# pressure_temp.net
KiCad netlist of a schematic drawn in EAGLE
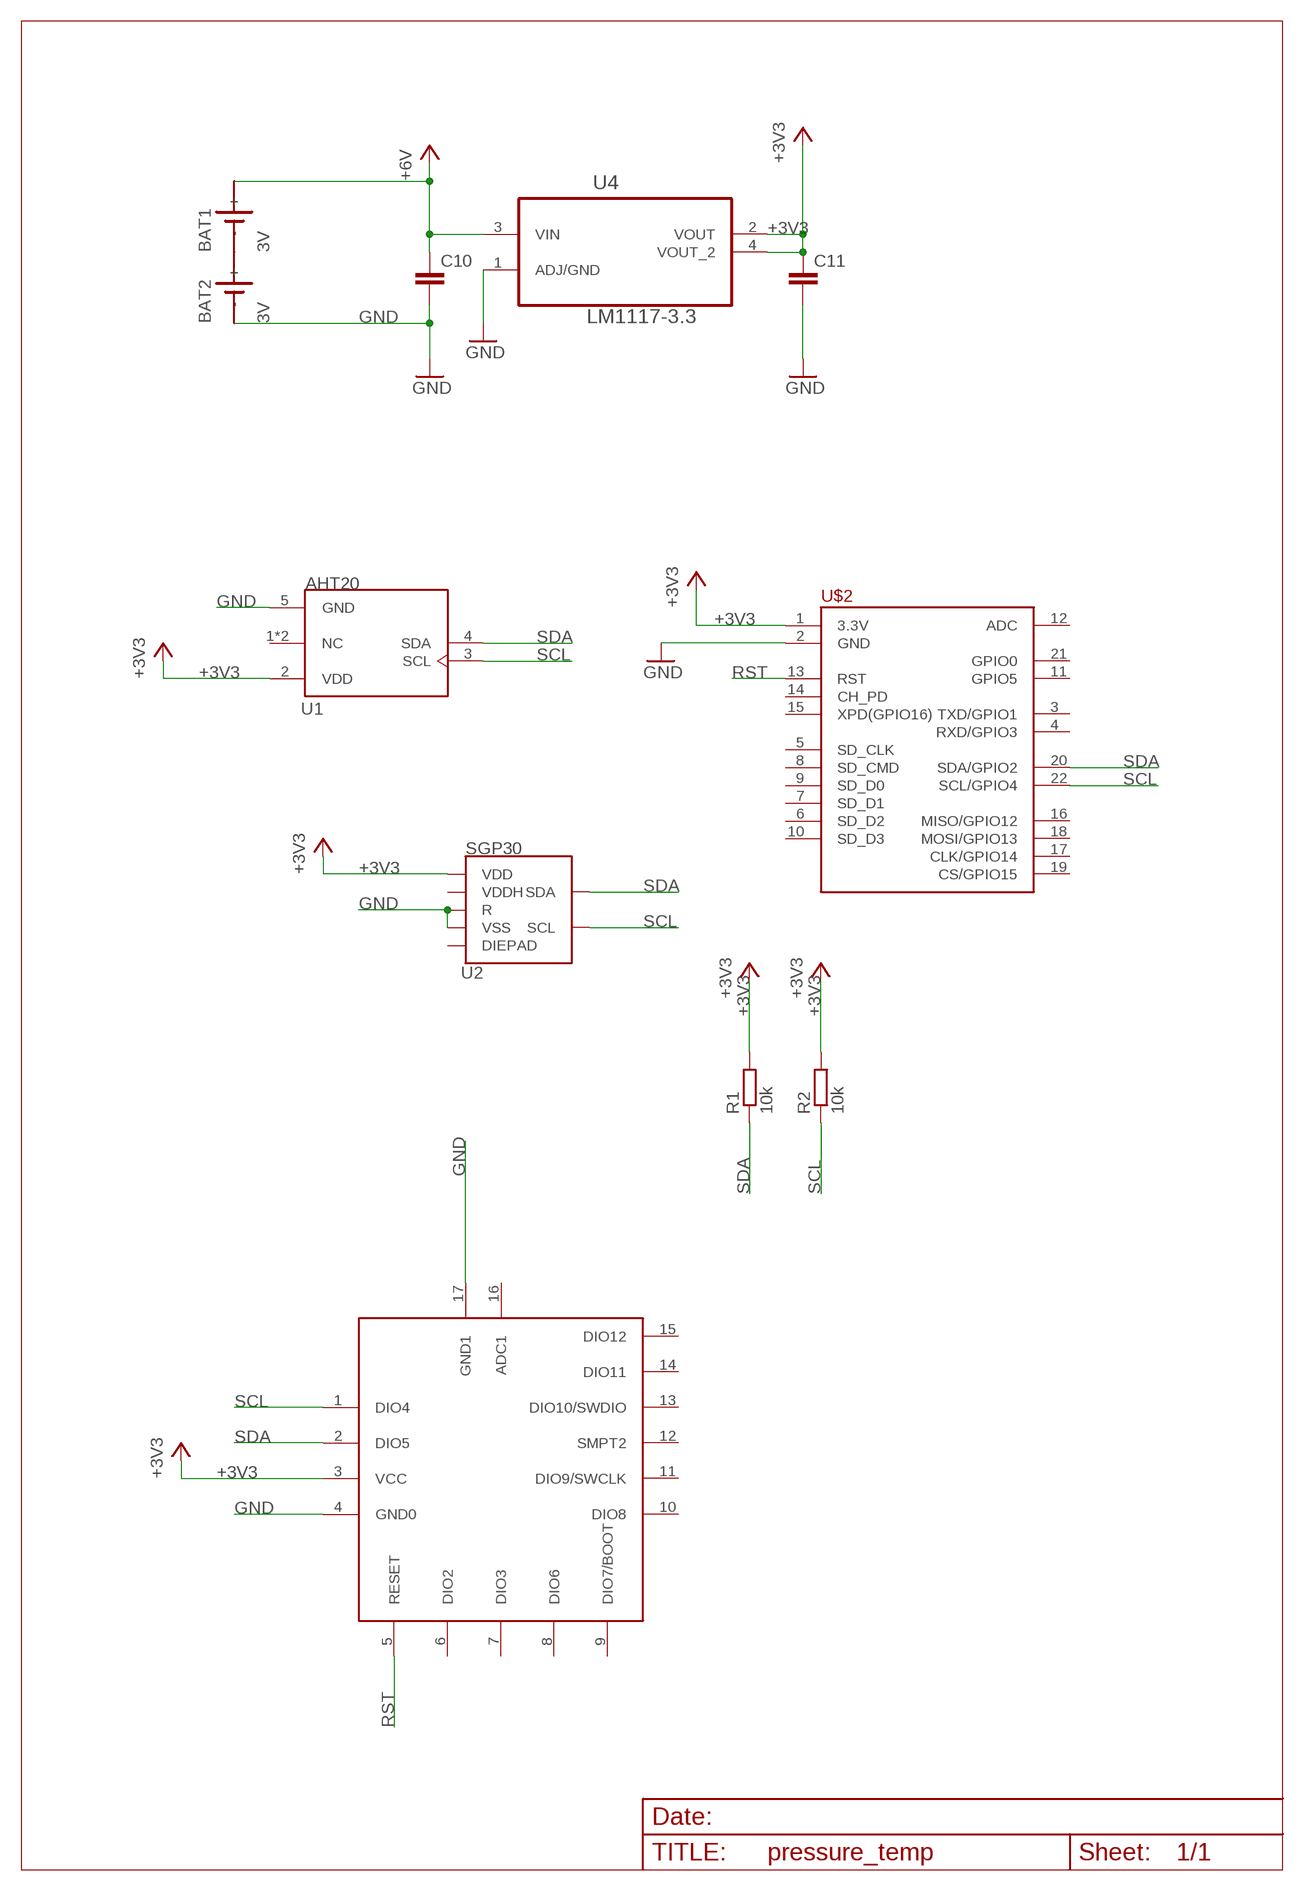
[diagram p0: schematic, sheet 1]

(export (version "E")
  (design (tool "Eeschema 10.0.6"))
  (components
    (comp (ref "BAT1")
      (value "3V")
      (footprint "eagle-import:SN2032")
      (libsource (lib "eagle-import") (part "SN2032"))
    )
    (comp (ref "BAT2")
      (value "3V")
      (footprint "eagle-import:SN2032")
      (libsource (lib "eagle-import") (part "SN2032"))
    )
    (comp (ref "C10")
      (value "47u")
      (footprint "eagle-import:C1206")
      (libsource (lib "eagle-import") (part "C-EUC1206"))
    )
    (comp (ref "C11")
      (value "10u")
      (footprint "eagle-import:C1206")
      (libsource (lib "eagle-import") (part "C-EUC1206"))
    )
    (comp (ref "R1")
      (value "10k")
      (footprint "eagle-import:R0402")
      (libsource (lib "eagle-import") (part "R-EU_R0402"))
    )
    (comp (ref "R2")
      (value "10k")
      (footprint "eagle-import:R0402")
      (libsource (lib "eagle-import") (part "R-EU_R0402"))
    )
    (comp (ref "U$1")
      (value "BLUENRG-234BLEMODULE")
      (footprint "eagle-import:BLUENRG-234BLEMODULE")
      (libsource (lib "eagle-import") (part "BLUENRG-234BLEMODULE"))
    )
    (comp (ref "U$2")
      (value "OLIMEX_MOD-WIFI-ESP8266-DEV>PINS-OUTSIDE")
      (footprint "eagle-import:OLIMEX_MOD-WIFI-ESP8266-DEV-PINS-OUTSIDE")
      (libsource (lib "eagle-import") (part "OLIMEX_MOD-WIFI-ESP8266-DEV{gt}PINS-OUTSIDE"))
    )
    (comp (ref "U1")
      (value "AHT20")
      (footprint "eagle-import:PSON100P300X300X110-6N")
      (fields (field (name "MF") "Asair"))
      (libsource (lib "eagle-import") (part "AHT20"))
    )
    (comp (ref "U2")
      (value "SGP30")
      (footprint "eagle-import:SGP30")
      (fields (field (name "MF") "Sensirion AG"))
      (libsource (lib "eagle-import") (part "SGP30"))
    )
    (comp (ref "U4")
      (value "LM1117-3.3")
      (footprint "eagle-import:SOT230")
      (fields (field (name "MF") "Texas Instruments"))
      (libsource (lib "eagle-import") (part "LM1117-3.3"))
    )
  )
  (nets
    (net (code "1") (name "+3V3") (class "Default")
      (node (ref "C11") (pin "1") (pinfunction "1_1") (pintype "passive"))
      (node (ref "R1") (pin "2") (pinfunction "2_2") (pintype "passive"))
      (node (ref "R2") (pin "2") (pinfunction "2_2") (pintype "passive"))
      (node (ref "U$1") (pin "3") (pinfunction "VCC_3") (pintype "bidirectional"))
      (node (ref "U$2") (pin "1") (pinfunction "3.3V_1") (pintype "power_in"))
      (node (ref "U1") (pin "2") (pinfunction "VDD_2") (pintype "power_in"))
      (node (ref "U2") (pin "1") (pinfunction "VDD_1") (pintype "bidirectional"))
      (node (ref "U4") (pin "2") (pinfunction "VOUT_2") (pintype "output"))
      (node (ref "U4") (pin "4") (pinfunction "VOUT_2_4") (pintype "output"))
    )
    (net (code "2") (name "+6V") (class "Default")
      (node (ref "BAT1") (pin "+") (pinfunction "+_+") (pintype "passive"))
      (node (ref "C10") (pin "1") (pinfunction "1_1") (pintype "passive"))
      (node (ref "U4") (pin "3") (pinfunction "VIN_3") (pintype "input"))
    )
    (net (code "3") (name "/RST") (class "Default")
      (node (ref "U$1") (pin "5") (pinfunction "RESET_5") (pintype "bidirectional"))
      (node (ref "U$2") (pin "13") (pinfunction "RST_13") (pintype "input"))
    )
    (net (code "4") (name "/SCL") (class "Default")
      (node (ref "R2") (pin "1") (pinfunction "1_1") (pintype "passive"))
      (node (ref "U$1") (pin "1") (pinfunction "DIO4_1") (pintype "bidirectional"))
      (node (ref "U$2") (pin "22") (pinfunction "SCL/GPIO4_22") (pintype "bidirectional"))
      (node (ref "U1") (pin "3") (pinfunction "SCL_3") (pintype "input"))
      (node (ref "U2") (pin "6") (pinfunction "SCL_6") (pintype "bidirectional"))
    )
    (net (code "5") (name "/SDA") (class "Default")
      (node (ref "R1") (pin "1") (pinfunction "1_1") (pintype "passive"))
      (node (ref "U$1") (pin "2") (pinfunction "DIO5_2") (pintype "bidirectional"))
      (node (ref "U$2") (pin "20") (pinfunction "SDA/GPIO2_20") (pintype "bidirectional"))
      (node (ref "U1") (pin "4") (pinfunction "SDA_4") (pintype "bidirectional"))
      (node (ref "U2") (pin "3") (pinfunction "SDA_3") (pintype "bidirectional"))
    )
    (net (code "6") (name "GND") (class "Default")
      (node (ref "BAT2") (pin "-") (pinfunction "-_-") (pintype "passive"))
      (node (ref "C10") (pin "2") (pinfunction "2_2") (pintype "passive"))
      (node (ref "C11") (pin "2") (pinfunction "2_2") (pintype "passive"))
      (node (ref "U$1") (pin "17") (pinfunction "GND1_17") (pintype "bidirectional"))
      (node (ref "U$1") (pin "4") (pinfunction "GND0_4") (pintype "bidirectional"))
      (node (ref "U$2") (pin "2") (pinfunction "GND_2") (pintype "power_in"))
      (node (ref "U1") (pin "5") (pinfunction "GND_5") (pintype "power_in"))
      (node (ref "U2") (pin "2") (pinfunction "VSS_2") (pintype "bidirectional"))
      (node (ref "U2") (pin "4") (pinfunction "R_4") (pintype "bidirectional"))
      (node (ref "U4") (pin "1") (pinfunction "ADJ/GND_1") (pintype "passive"))
    )
    (net (code "7") (name "Net-(BAT1-Pad-)") (class "Default")
      (node (ref "BAT1") (pin "-") (pinfunction "-_-") (pintype "passive"))
      (node (ref "BAT2") (pin "+") (pinfunction "+_+") (pintype "passive"))
    )
    (net (code "8") (name "unconnected-(U$1-ADC1-Pad16)") (class "Default")
      (node (ref "U$1") (pin "16") (pinfunction "ADC1_16") (pintype "bidirectional"))
    )
    (net (code "9") (name "unconnected-(U$1-DIO2-Pad6)") (class "Default")
      (node (ref "U$1") (pin "6") (pinfunction "DIO2_6") (pintype "bidirectional"))
    )
    (net (code "10") (name "unconnected-(U$1-DIO3-Pad7)") (class "Default")
      (node (ref "U$1") (pin "7") (pinfunction "DIO3_7") (pintype "bidirectional"))
    )
    (net (code "11") (name "unconnected-(U$1-DIO6-Pad8)") (class "Default")
      (node (ref "U$1") (pin "8") (pinfunction "DIO6_8") (pintype "bidirectional"))
    )
    (net (code "12") (name "unconnected-(U$1-DIO7{slash}BOOT-Pad9)") (class "Default")
      (node (ref "U$1") (pin "9") (pinfunction "DIO7/BOOT_9") (pintype "bidirectional"))
    )
    (net (code "13") (name "unconnected-(U$1-DIO8-Pad10)") (class "Default")
      (node (ref "U$1") (pin "10") (pinfunction "DIO8_10") (pintype "bidirectional"))
    )
    (net (code "14") (name "unconnected-(U$1-DIO9{slash}SWCLK-Pad11)") (class "Default")
      (node (ref "U$1") (pin "11") (pinfunction "DIO9/SWCLK_11") (pintype "bidirectional"))
    )
    (net (code "15") (name "unconnected-(U$1-DIO10{slash}SWDIO-Pad13)") (class "Default")
      (node (ref "U$1") (pin "13") (pinfunction "DIO10/SWDIO_13") (pintype "bidirectional"))
    )
    (net (code "16") (name "unconnected-(U$1-DIO11-Pad14)") (class "Default")
      (node (ref "U$1") (pin "14") (pinfunction "DIO11_14") (pintype "bidirectional"))
    )
    (net (code "17") (name "unconnected-(U$1-DIO12-Pad15)") (class "Default")
      (node (ref "U$1") (pin "15") (pinfunction "DIO12_15") (pintype "bidirectional"))
    )
    (net (code "18") (name "unconnected-(U$1-SMPT2-Pad12)") (class "Default")
      (node (ref "U$1") (pin "12") (pinfunction "SMPT2_12") (pintype "bidirectional"))
    )
    (net (code "19") (name "unconnected-(U$2-ADC-Pad12)") (class "Default")
      (node (ref "U$2") (pin "12") (pinfunction "ADC_12") (pintype "bidirectional"))
    )
    (net (code "20") (name "unconnected-(U$2-CH_PD-Pad14)") (class "Default")
      (node (ref "U$2") (pin "14") (pinfunction "CH_PD_14") (pintype "input"))
    )
    (net (code "21") (name "unconnected-(U$2-CLK{slash}GPIO14-Pad17)") (class "Default")
      (node (ref "U$2") (pin "17") (pinfunction "CLK/GPIO14_17") (pintype "bidirectional"))
    )
    (net (code "22") (name "unconnected-(U$2-CS{slash}GPIO15-Pad19)") (class "Default")
      (node (ref "U$2") (pin "19") (pinfunction "CS/GPIO15_19") (pintype "bidirectional"))
    )
    (net (code "23") (name "unconnected-(U$2-GPIO0-Pad21)") (class "Default")
      (node (ref "U$2") (pin "21") (pinfunction "GPIO0_21") (pintype "bidirectional"))
    )
    (net (code "24") (name "unconnected-(U$2-GPIO5-Pad11)") (class "Default")
      (node (ref "U$2") (pin "11") (pinfunction "GPIO5_11") (pintype "bidirectional"))
    )
    (net (code "25") (name "unconnected-(U$2-MISO{slash}GPIO12-Pad16)") (class "Default")
      (node (ref "U$2") (pin "16") (pinfunction "MISO/GPIO12_16") (pintype "bidirectional"))
    )
    (net (code "26") (name "unconnected-(U$2-MOSI{slash}GPIO13-Pad18)") (class "Default")
      (node (ref "U$2") (pin "18") (pinfunction "MOSI/GPIO13_18") (pintype "bidirectional"))
    )
    (net (code "27") (name "unconnected-(U$2-RXD{slash}GPIO3-Pad4)") (class "Default")
      (node (ref "U$2") (pin "4") (pinfunction "RXD/GPIO3_4") (pintype "bidirectional"))
    )
    (net (code "28") (name "unconnected-(U$2-SD_CLK-Pad5)") (class "Default")
      (node (ref "U$2") (pin "5") (pinfunction "SD_CLK_5") (pintype "bidirectional"))
    )
    (net (code "29") (name "unconnected-(U$2-SD_CMD-Pad8)") (class "Default")
      (node (ref "U$2") (pin "8") (pinfunction "SD_CMD_8") (pintype "bidirectional"))
    )
    (net (code "30") (name "unconnected-(U$2-SD_D0-Pad9)") (class "Default")
      (node (ref "U$2") (pin "9") (pinfunction "SD_D0_9") (pintype "bidirectional"))
    )
    (net (code "31") (name "unconnected-(U$2-SD_D1-Pad7)") (class "Default")
      (node (ref "U$2") (pin "7") (pinfunction "SD_D1_7") (pintype "bidirectional"))
    )
    (net (code "32") (name "unconnected-(U$2-SD_D2-Pad6)") (class "Default")
      (node (ref "U$2") (pin "6") (pinfunction "SD_D2_6") (pintype "bidirectional"))
    )
    (net (code "33") (name "unconnected-(U$2-SD_D3-Pad10)") (class "Default")
      (node (ref "U$2") (pin "10") (pinfunction "SD_D3_10") (pintype "bidirectional"))
    )
    (net (code "34") (name "unconnected-(U$2-TXD{slash}GPIO1-Pad3)") (class "Default")
      (node (ref "U$2") (pin "3") (pinfunction "TXD/GPIO1_3") (pintype "bidirectional"))
    )
    (net (code "35") (name "unconnected-(U$2-XPD(GPIO16)-Pad15)") (class "Default")
      (node (ref "U$2") (pin "15") (pinfunction "XPD(GPIO16)_15") (pintype "bidirectional"))
    )
    (net (code "36") (name "unconnected-(U1-NC-Pad1)") (class "Default")
      (node (ref "U1") (pin "1") (pinfunction "NC_1") (pintype "no_connect"))
    )
    (net (code "37") (name "unconnected-(U1-NC-Pad6)") (class "Default")
      (node (ref "U1") (pin "6") (pinfunction "NC_6") (pintype "no_connect"))
    )
    (net (code "38") (name "unconnected-(U2-PadDIEPAD)") (class "Default")
      (node (ref "U2") (pin "DIEPAD") (pinfunction "DIEPAD_DIEPAD") (pintype "bidirectional"))
    )
    (net (code "39") (name "unconnected-(U2-VDDH-Pad5)") (class "Default")
      (node (ref "U2") (pin "5") (pinfunction "VDDH_5") (pintype "bidirectional"))
    )
  )
)
